# v0_5_0.net
KiCad netlist of a schematic drawn in EAGLE
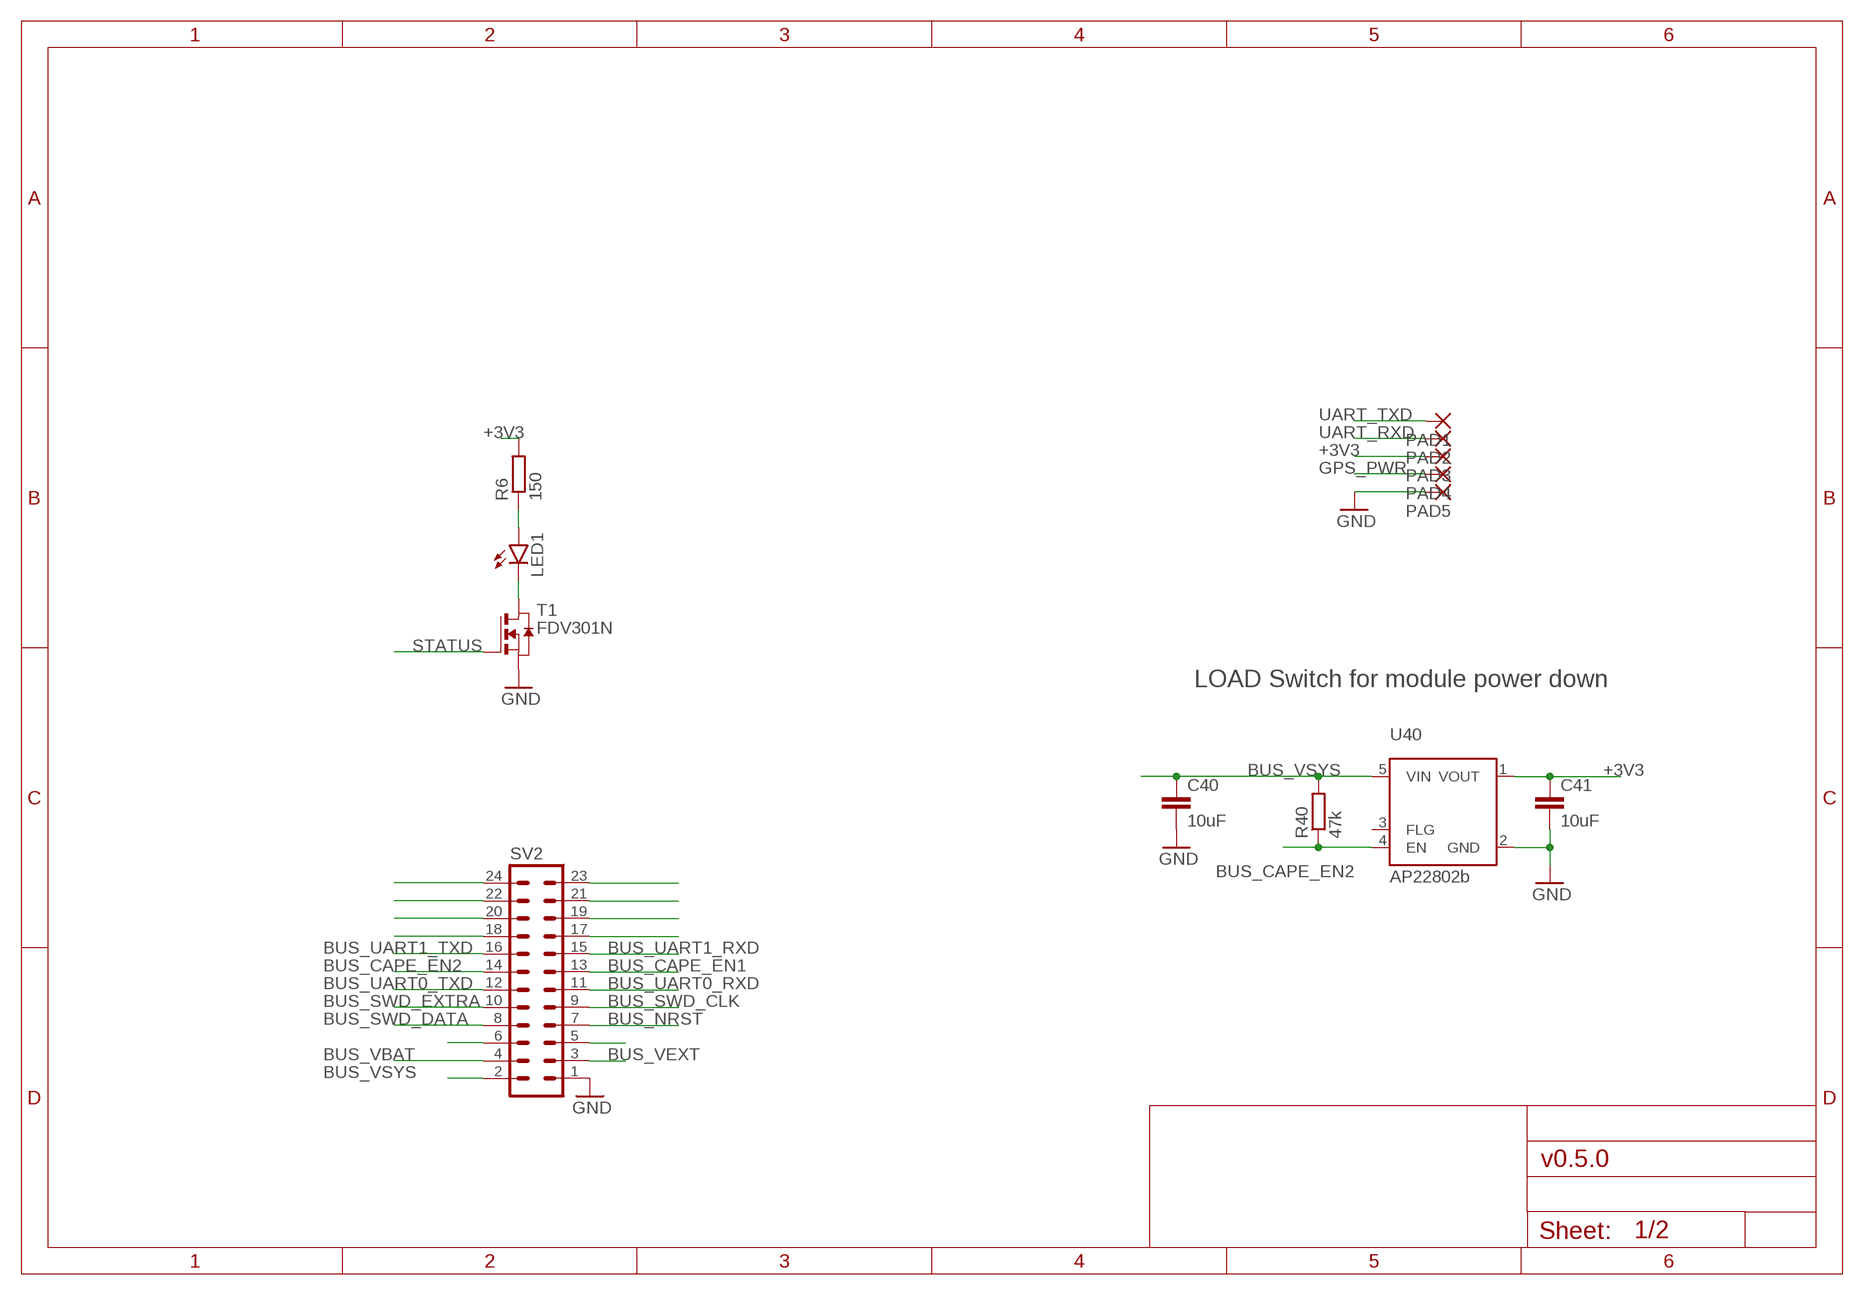
[diagram p0: schematic, sheet 1]
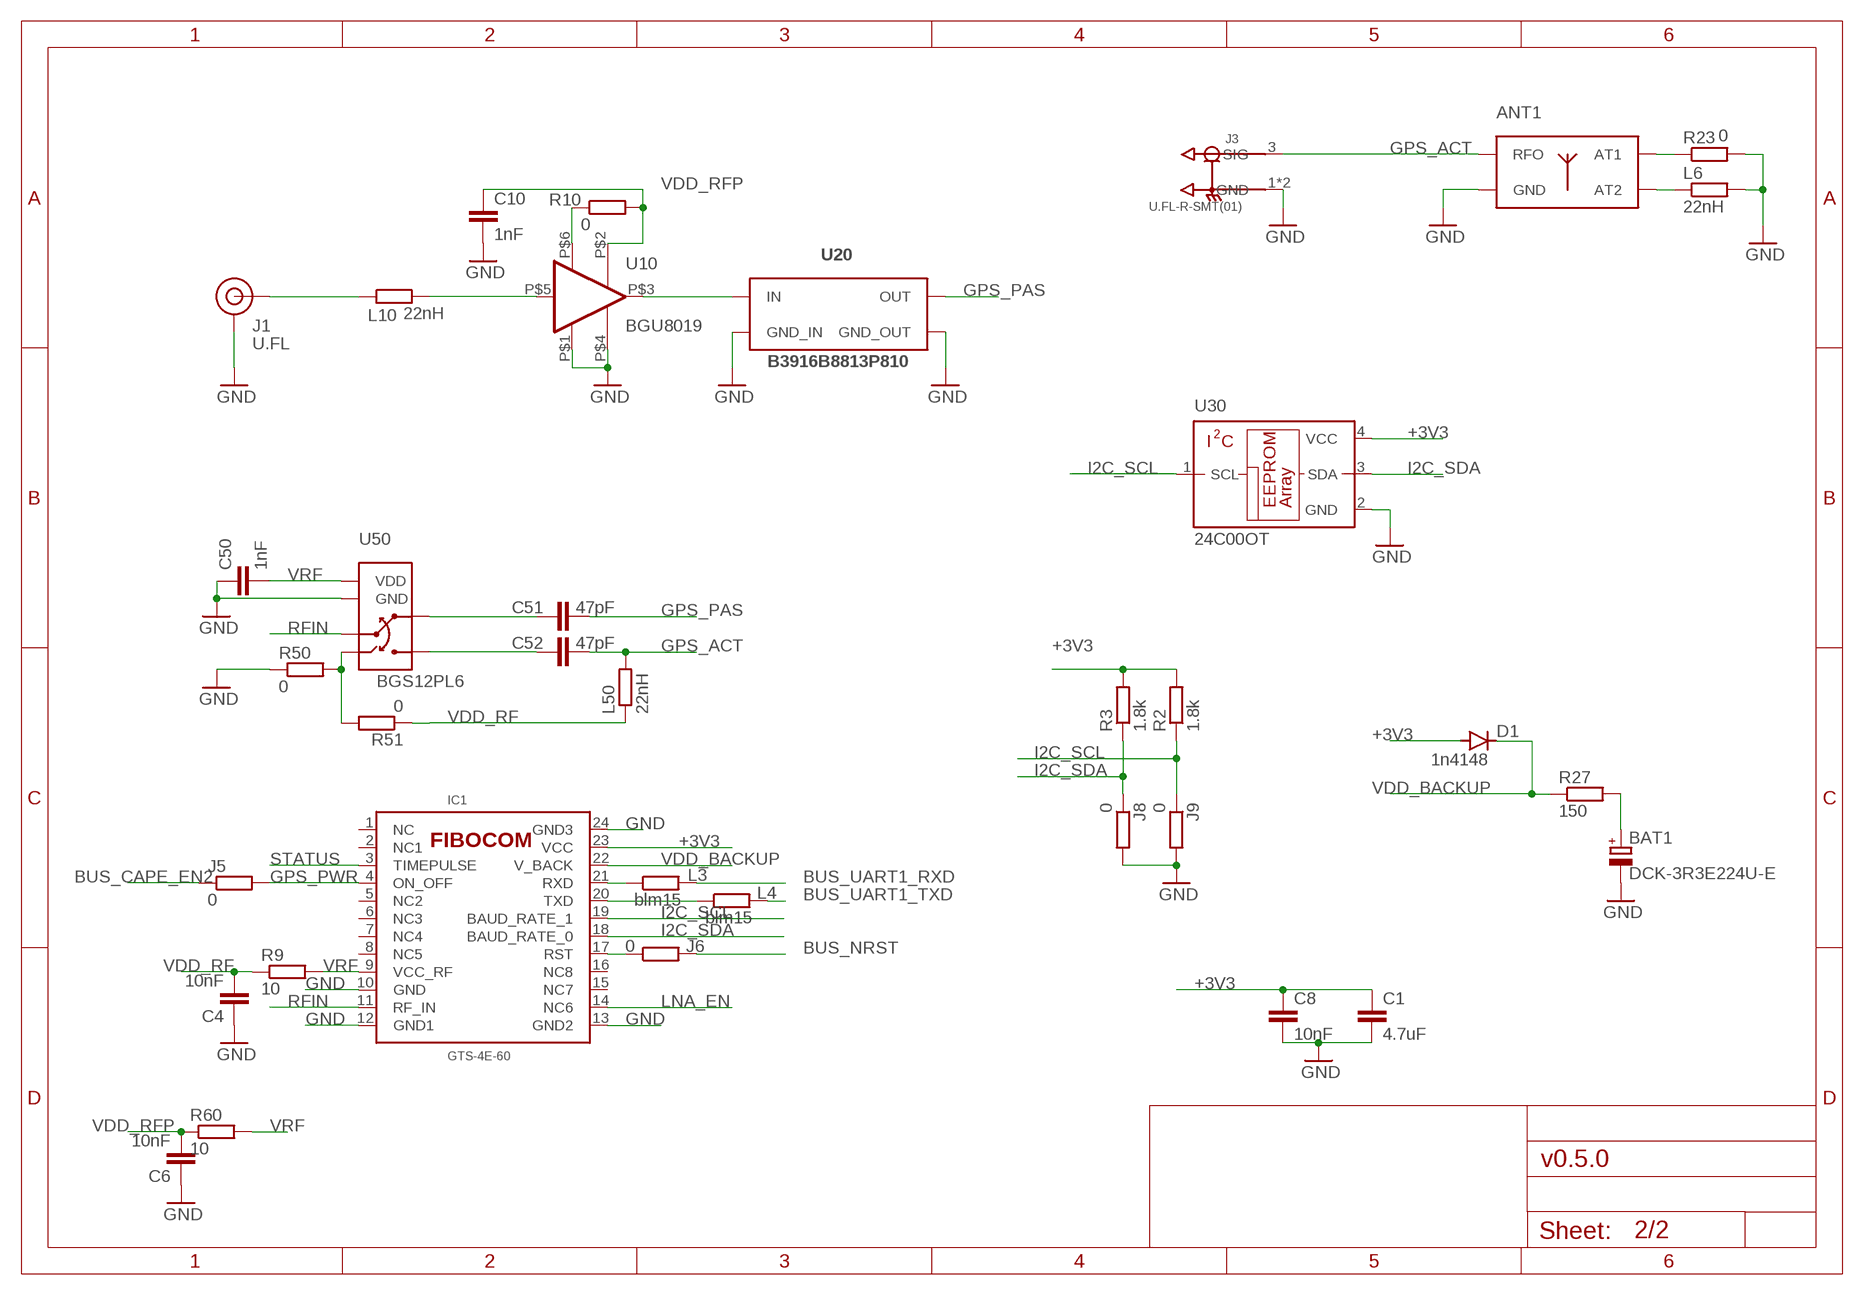
[diagram p1: schematic, sheet 2]

(export (version "E")
  (design (tool "Eeschema 10.0.6"))
  (components
    (comp (ref "C40")
      (value "10uF")
      (footprint "eagle-import:C0603")
      (libsource (lib "eagle-import") (part "C-EUC0603"))
    )
    (comp (ref "C41")
      (value "10uF")
      (footprint "eagle-import:C0603")
      (libsource (lib "eagle-import") (part "C-EUC0603"))
    )
    (comp (ref "LED1")
      (value "LEDCHIP-LED0603")
      (footprint "eagle-import:CHIP-LED0603")
      (libsource (lib "eagle-import") (part "LEDCHIP-LED0603"))
    )
    (comp (ref "PAD1")
      (value "1,6/0,9")
      (footprint "eagle-import:1,6_0,9")
      (libsource (lib "eagle-import") (part "1,6/0,9"))
    )
    (comp (ref "PAD2")
      (value "1,6/0,9")
      (footprint "eagle-import:1,6_0,9")
      (libsource (lib "eagle-import") (part "1,6/0,9"))
    )
    (comp (ref "PAD3")
      (value "1,6/0,9")
      (footprint "eagle-import:1,6_0,9")
      (libsource (lib "eagle-import") (part "1,6/0,9"))
    )
    (comp (ref "PAD4")
      (value "1,6/0,9")
      (footprint "eagle-import:1,6_0,9")
      (libsource (lib "eagle-import") (part "1,6/0,9"))
    )
    (comp (ref "PAD5")
      (value "1,6/0,9")
      (footprint "eagle-import:1,6_0,9")
      (libsource (lib "eagle-import") (part "1,6/0,9"))
    )
    (comp (ref "R6")
      (value "150")
      (footprint "eagle-import:R0402")
      (libsource (lib "eagle-import") (part "R-EU_R0402"))
    )
    (comp (ref "R40")
      (value "47k")
      (footprint "eagle-import:R0402")
      (libsource (lib "eagle-import") (part "R-EU_R0402"))
    )
    (comp (ref "SV2")
      (value "MA12-2")
      (footprint "eagle-import:MA12-2")
      (libsource (lib "eagle-import") (part "MA12-2"))
    )
    (comp (ref "T1")
      (value "FDV301N")
      (footprint "eagle-import:SOT-23")
      (libsource (lib "eagle-import") (part "NMOSSOT23"))
    )
    (comp (ref "U40")
      (value "AP22802b")
      (footprint "eagle-import:SOT25")
      (libsource (lib "eagle-import") (part "AP22802"))
    )
    (comp (ref "ANT1")
      (value "M20047")
      (footprint "eagle-import:PCBCOMPONENT_1")
      (libsource (lib "eagle-import") (part "M20047"))
    )
    (comp (ref "BAT1")
      (value "DCK-3R3E224U-E")
      (footprint "eagle-import:621")
      (libsource (lib "eagle-import") (part "DCK-3R3E224U-E"))
    )
    (comp (ref "C1")
      (value "4.7uF")
      (footprint "eagle-import:C0603")
      (libsource (lib "eagle-import") (part "C-EUC0603"))
    )
    (comp (ref "C4")
      (value "10nF")
      (footprint "eagle-import:C0402")
      (libsource (lib "eagle-import") (part "C-EUC0402"))
    )
    (comp (ref "C6")
      (value "10nF")
      (footprint "eagle-import:C0402")
      (libsource (lib "eagle-import") (part "C-EUC0402"))
    )
    (comp (ref "C8")
      (value "10nF")
      (footprint "eagle-import:C0402")
      (libsource (lib "eagle-import") (part "C-EUC0402"))
    )
    (comp (ref "C10")
      (value "1nF")
      (footprint "eagle-import:C0402")
      (libsource (lib "eagle-import") (part "C-EUC0402"))
    )
    (comp (ref "C50")
      (value "1nF")
      (footprint "eagle-import:C0402")
      (libsource (lib "eagle-import") (part "C-EUC0402"))
    )
    (comp (ref "C51")
      (value "47pF")
      (footprint "eagle-import:C0402")
      (libsource (lib "eagle-import") (part "C-EUC0402"))
    )
    (comp (ref "C52")
      (value "47pF")
      (footprint "eagle-import:C0402")
      (libsource (lib "eagle-import") (part "C-EUC0402"))
    )
    (comp (ref "D1")
      (value "1n4148")
      (footprint "eagle-import:SOD323-R")
      (libsource (lib "eagle-import") (part "DIODE-SOD323-R"))
    )
    (comp (ref "IC1")
      (value "GTS-4E-60")
      (footprint "eagle-import:_GTS_4E_60")
      (libsource (lib "eagle-import") (part "GTS-4E-60"))
    )
    (comp (ref "J1")
      (value "U.FL")
      (footprint "eagle-import:U.FL")
      (libsource (lib "eagle-import") (part "U.FL2PIN"))
    )
    (comp (ref "J3")
      (value "U.FL-R-SMT(01)")
      (footprint "eagle-import:HRS_U.FL-R-SMT(01)")
      (fields (field (name "MF") "Hirose") (field (name "MP") "U.FL-R-SMT_01_"))
      (libsource (lib "eagle-import") (part "U.FL-R-SMT(01)"))
    )
    (comp (ref "J5")
      (value "0")
      (footprint "eagle-import:R0402")
      (libsource (lib "eagle-import") (part "R-EU_R0402"))
    )
    (comp (ref "J6")
      (value "0")
      (footprint "eagle-import:R0402")
      (libsource (lib "eagle-import") (part "R-EU_R0402"))
    )
    (comp (ref "J8")
      (value "0")
      (footprint "eagle-import:R0402")
      (libsource (lib "eagle-import") (part "R-EU_R0402"))
    )
    (comp (ref "J9")
      (value "0")
      (footprint "eagle-import:R0402")
      (libsource (lib "eagle-import") (part "R-EU_R0402"))
    )
    (comp (ref "L3")
      (value "blm15")
      (footprint "eagle-import:R0402")
      (libsource (lib "eagle-import") (part "R-EU_R0402"))
    )
    (comp (ref "L4")
      (value "blm15")
      (footprint "eagle-import:R0402")
      (libsource (lib "eagle-import") (part "R-EU_R0402"))
    )
    (comp (ref "L6")
      (value "22nH")
      (footprint "eagle-import:R0402")
      (libsource (lib "eagle-import") (part "R-EU_R0402"))
    )
    (comp (ref "L10")
      (value "22nH")
      (footprint "eagle-import:R0402")
      (libsource (lib "eagle-import") (part "R-EU_R0402"))
    )
    (comp (ref "L50")
      (value "22nH")
      (footprint "eagle-import:R0402")
      (libsource (lib "eagle-import") (part "R-EU_R0402"))
    )
    (comp (ref "R2")
      (value "1.8k")
      (footprint "eagle-import:R0402")
      (libsource (lib "eagle-import") (part "R-EU_R0402"))
    )
    (comp (ref "R3")
      (value "1.8k")
      (footprint "eagle-import:R0402")
      (libsource (lib "eagle-import") (part "R-EU_R0402"))
    )
    (comp (ref "R9")
      (value "10")
      (footprint "eagle-import:R0402")
      (libsource (lib "eagle-import") (part "R-EU_R0402"))
    )
    (comp (ref "R10")
      (value "0")
      (footprint "eagle-import:R0402")
      (libsource (lib "eagle-import") (part "R-EU_R0402"))
    )
    (comp (ref "R23")
      (value "0")
      (footprint "eagle-import:R0402")
      (libsource (lib "eagle-import") (part "R-EU_R0402"))
    )
    (comp (ref "R27")
      (value "150")
      (footprint "eagle-import:R0402")
      (libsource (lib "eagle-import") (part "R-EU_R0402"))
    )
    (comp (ref "R50")
      (value "0")
      (footprint "eagle-import:R0402")
      (libsource (lib "eagle-import") (part "R-EU_R0402"))
    )
    (comp (ref "R51")
      (value "0")
      (footprint "eagle-import:R0402")
      (libsource (lib "eagle-import") (part "R-EU_R0402"))
    )
    (comp (ref "R60")
      (value "10")
      (footprint "eagle-import:R0402")
      (libsource (lib "eagle-import") (part "R-EU_R0402"))
    )
    (comp (ref "U10")
      (value "BGU8019")
      (footprint "eagle-import:XSON6")
      (libsource (lib "eagle-import") (part "BGU8019"))
    )
    (comp (ref "U20")
      (value "B3916B8813P810")
      (footprint "eagle-import:XSON5")
      (libsource (lib "eagle-import") (part "B3916B8813P810"))
    )
    (comp (ref "U30")
      (value "24C00OT")
      (footprint "eagle-import:SOT23-5L")
      (fields (field (name "MF") "MICROCHIP") (field (name "MPN") "24C00T-I/OT"))
      (libsource (lib "eagle-import") (part "2400OTC"))
    )
    (comp (ref "U50")
      (value "BGS12PL6")
      (footprint "eagle-import:TSLP-6-4")
      (libsource (lib "eagle-import") (part "BGS12PL6"))
    )
  )
  (nets
    (net (code "1") (name "+3V3") (class "Default")
      (node (ref "C1") (pin "1") (pinfunction "1_1") (pintype "passive"))
      (node (ref "C41") (pin "1") (pinfunction "1_1") (pintype "passive"))
      (node (ref "C8") (pin "1") (pinfunction "1_1") (pintype "passive"))
      (node (ref "D1") (pin "A") (pinfunction "A_A") (pintype "passive"))
      (node (ref "IC1") (pin "23") (pinfunction "VCC_23") (pintype "bidirectional"))
      (node (ref "PAD3") (pin "1") (pinfunction "P_1") (pintype "passive"))
      (node (ref "R2") (pin "2") (pinfunction "2_2") (pintype "passive"))
      (node (ref "R3") (pin "2") (pinfunction "2_2") (pintype "passive"))
      (node (ref "R6") (pin "2") (pinfunction "2_2") (pintype "passive"))
      (node (ref "U30") (pin "4") (pinfunction "VCC_4") (pintype "power_in"))
      (node (ref "U40") (pin "1") (pinfunction "VOUT_1") (pintype "bidirectional"))
    )
    (net (code "2") (name "BUS_CAPE_EN1") (class "Default")
      (node (ref "SV2") (pin "13") (pinfunction "13_13") (pintype "passive"))
    )
    (net (code "3") (name "BUS_CAPE_EN2") (class "Default")
      (node (ref "J5") (pin "1") (pinfunction "1_1") (pintype "passive"))
      (node (ref "R40") (pin "1") (pinfunction "1_1") (pintype "passive"))
      (node (ref "SV2") (pin "14") (pinfunction "14_14") (pintype "passive"))
      (node (ref "U40") (pin "4") (pinfunction "EN_4") (pintype "bidirectional"))
    )
    (net (code "4") (name "BUS_NRST") (class "Default")
      (node (ref "J6") (pin "2") (pinfunction "2_2") (pintype "passive"))
      (node (ref "SV2") (pin "7") (pinfunction "7_7") (pintype "passive"))
    )
    (net (code "5") (name "BUS_SWD_CLK") (class "Default")
      (node (ref "SV2") (pin "9") (pinfunction "9_9") (pintype "passive"))
    )
    (net (code "6") (name "BUS_SWD_DATA") (class "Default")
      (node (ref "SV2") (pin "8") (pinfunction "8_8") (pintype "passive"))
    )
    (net (code "7") (name "BUS_SWD_EXTRA") (class "Default")
      (node (ref "SV2") (pin "10") (pinfunction "10_10") (pintype "passive"))
    )
    (net (code "8") (name "BUS_UART0_RXD") (class "Default")
      (node (ref "SV2") (pin "11") (pinfunction "11_11") (pintype "passive"))
    )
    (net (code "9") (name "BUS_UART0_TXD") (class "Default")
      (node (ref "SV2") (pin "12") (pinfunction "12_12") (pintype "passive"))
    )
    (net (code "10") (name "BUS_UART1_RXD") (class "Default")
      (node (ref "L3") (pin "2") (pinfunction "2_2") (pintype "passive"))
      (node (ref "SV2") (pin "15") (pinfunction "15_15") (pintype "passive"))
    )
    (net (code "11") (name "BUS_UART1_TXD") (class "Default")
      (node (ref "L4") (pin "2") (pinfunction "2_2") (pintype "passive"))
      (node (ref "SV2") (pin "16") (pinfunction "16_16") (pintype "passive"))
    )
    (net (code "12") (name "BUS_VBAT") (class "Default")
      (node (ref "SV2") (pin "4") (pinfunction "4_4") (pintype "passive"))
    )
    (net (code "13") (name "BUS_VEXT") (class "Default")
      (node (ref "SV2") (pin "3") (pinfunction "3_3") (pintype "passive"))
    )
    (net (code "14") (name "BUS_VSYS") (class "Default")
      (node (ref "C40") (pin "1") (pinfunction "1_1") (pintype "passive"))
      (node (ref "R40") (pin "2") (pinfunction "2_2") (pintype "passive"))
      (node (ref "SV2") (pin "2") (pinfunction "2_2") (pintype "passive"))
      (node (ref "U40") (pin "5") (pinfunction "VIN_5") (pintype "bidirectional"))
    )
    (net (code "15") (name "GND") (class "Default")
      (node (ref "ANT1") (pin "2") (pinfunction "GND_2") (pintype "power_in"))
      (node (ref "ANT1") (pin "3") (pinfunction "GND_3") (pintype "power_in"))
      (node (ref "ANT1") (pin "4") (pinfunction "GND_4") (pintype "power_in"))
      (node (ref "BAT1") (pin "-") (pinfunction "-_-") (pintype "passive"))
      (node (ref "C1") (pin "2") (pinfunction "2_2") (pintype "passive"))
      (node (ref "C10") (pin "2") (pinfunction "2_2") (pintype "passive"))
      (node (ref "C4") (pin "1") (pinfunction "1_1") (pintype "passive"))
      (node (ref "C40") (pin "2") (pinfunction "2_2") (pintype "passive"))
      (node (ref "C41") (pin "2") (pinfunction "2_2") (pintype "passive"))
      (node (ref "C50") (pin "1") (pinfunction "1_1") (pintype "passive"))
      (node (ref "C6") (pin "1") (pinfunction "1_1") (pintype "passive"))
      (node (ref "C8") (pin "2") (pinfunction "2_2") (pintype "passive"))
      (node (ref "IC1") (pin "10") (pinfunction "GND_10") (pintype "bidirectional"))
      (node (ref "IC1") (pin "12") (pinfunction "GND1_12") (pintype "bidirectional"))
      (node (ref "IC1") (pin "13") (pinfunction "GND2_13") (pintype "bidirectional"))
      (node (ref "IC1") (pin "24") (pinfunction "GND3_24") (pintype "bidirectional"))
      (node (ref "J1") (pin "1") (pinfunction "GND_1") (pintype "bidirectional"))
      (node (ref "J1") (pin "2") (pinfunction "GND_2") (pintype "bidirectional"))
      (node (ref "J3") (pin "1") (pinfunction "GND_1") (pintype "passive"))
      (node (ref "J3") (pin "2") (pinfunction "GND_2") (pintype "passive"))
      (node (ref "J8") (pin "2") (pinfunction "2_2") (pintype "passive"))
      (node (ref "J9") (pin "2") (pinfunction "2_2") (pintype "passive"))
      (node (ref "L6") (pin "2") (pinfunction "2_2") (pintype "passive"))
      (node (ref "PAD5") (pin "1") (pinfunction "P_1") (pintype "passive"))
      (node (ref "R23") (pin "2") (pinfunction "2_2") (pintype "passive"))
      (node (ref "R50") (pin "1") (pinfunction "1_1") (pintype "passive"))
      (node (ref "SV2") (pin "1") (pinfunction "1_1") (pintype "passive"))
      (node (ref "T1") (pin "2") (pinfunction "S_2") (pintype "passive"))
      (node (ref "U10") (pin "P$1") (pinfunction "GND_P$1") (pintype "power_in"))
      (node (ref "U10") (pin "P$4") (pinfunction "GND_RF_P$4") (pintype "passive"))
      (node (ref "U20") (pin "2") (pinfunction "GND_IN_2") (pintype "bidirectional"))
      (node (ref "U20") (pin "3") (pinfunction "GND_OUT_3") (pintype "bidirectional"))
      (node (ref "U20") (pin "5") (pinfunction "GND_IN_5") (pintype "bidirectional"))
      (node (ref "U30") (pin "2") (pinfunction "GND_2") (pintype "power_in"))
      (node (ref "U40") (pin "2") (pinfunction "GND_2") (pintype "bidirectional"))
      (node (ref "U50") (pin "P$2") (pinfunction "GND_P$2") (pintype "power_in"))
    )
    (net (code "16") (name "GPS_ACT") (class "Default")
      (node (ref "ANT1") (pin "5") (pinfunction "RFO_5") (pintype "input"))
      (node (ref "C52") (pin "2") (pinfunction "2_2") (pintype "passive"))
      (node (ref "J3") (pin "3") (pinfunction "SIG_3") (pintype "passive"))
      (node (ref "L50") (pin "2") (pinfunction "2_2") (pintype "passive"))
    )
    (net (code "17") (name "GPS_PAS") (class "Default")
      (node (ref "C51") (pin "2") (pinfunction "2_2") (pintype "passive"))
      (node (ref "U20") (pin "4") (pinfunction "OUT_4") (pintype "bidirectional"))
    )
    (net (code "18") (name "GPS_PWR") (class "Default")
      (node (ref "IC1") (pin "4") (pinfunction "ON_OFF_4") (pintype "bidirectional"))
      (node (ref "J5") (pin "2") (pinfunction "2_2") (pintype "passive"))
      (node (ref "PAD4") (pin "1") (pinfunction "P_1") (pintype "passive"))
    )
    (net (code "19") (name "I2C_SCL") (class "Default")
      (node (ref "IC1") (pin "19") (pinfunction "BAUD_RATE_1_19") (pintype "bidirectional"))
      (node (ref "J9") (pin "1") (pinfunction "1_1") (pintype "passive"))
      (node (ref "R2") (pin "1") (pinfunction "1_1") (pintype "passive"))
      (node (ref "U30") (pin "1") (pinfunction "SCL_1") (pintype "input"))
    )
    (net (code "20") (name "I2C_SDA") (class "Default")
      (node (ref "IC1") (pin "18") (pinfunction "BAUD_RATE_0_18") (pintype "bidirectional"))
      (node (ref "J8") (pin "1") (pinfunction "1_1") (pintype "passive"))
      (node (ref "R3") (pin "1") (pinfunction "1_1") (pintype "passive"))
      (node (ref "U30") (pin "3") (pinfunction "SDA_3") (pintype "bidirectional"))
    )
    (net (code "21") (name "LNA_EN") (class "Default")
      (node (ref "IC1") (pin "14") (pinfunction "NC6_14") (pintype "bidirectional"))
    )
    (net (code "22") (name "Net-(ANT1-AT1)") (class "Default")
      (node (ref "ANT1") (pin "1") (pinfunction "AT1_1") (pintype "bidirectional"))
      (node (ref "R23") (pin "1") (pinfunction "1_1") (pintype "passive"))
    )
    (net (code "23") (name "Net-(ANT1-AT2)") (class "Default")
      (node (ref "ANT1") (pin "6") (pinfunction "AT2_6") (pintype "bidirectional"))
      (node (ref "L6") (pin "1") (pinfunction "1_1") (pintype "passive"))
    )
    (net (code "24") (name "Net-(BAT1-Pad+)") (class "Default")
      (node (ref "BAT1") (pin "+") (pinfunction "+_+") (pintype "passive"))
      (node (ref "R27") (pin "2") (pinfunction "2_2") (pintype "passive"))
    )
    (net (code "25") (name "Net-(IC1-RST)") (class "Default")
      (node (ref "IC1") (pin "17") (pinfunction "RST_17") (pintype "bidirectional"))
      (node (ref "J6") (pin "1") (pinfunction "1_1") (pintype "passive"))
    )
    (net (code "26") (name "Net-(J1-SIGNAL)") (class "Default")
      (node (ref "J1") (pin "FEED") (pinfunction "SIGNAL_FEED") (pintype "bidirectional"))
      (node (ref "L10") (pin "1") (pinfunction "1_1") (pintype "passive"))
    )
    (net (code "27") (name "Net-(LED1-PadA)") (class "Default")
      (node (ref "LED1") (pin "A") (pinfunction "A_A") (pintype "passive"))
      (node (ref "R6") (pin "1") (pinfunction "1_1") (pintype "passive"))
    )
    (net (code "28") (name "Net-(T1-D)") (class "Default")
      (node (ref "LED1") (pin "C") (pinfunction "C_C") (pintype "passive"))
      (node (ref "T1") (pin "1") (pinfunction "D_1") (pintype "passive"))
    )
    (net (code "29") (name "Net-(U10-ENABLE)") (class "Default")
      (node (ref "R10") (pin "1") (pinfunction "1_1") (pintype "passive"))
      (node (ref "U10") (pin "P$6") (pinfunction "ENABLE_P$6") (pintype "power_in"))
    )
    (net (code "30") (name "Net-(U10-RF_IN)") (class "Default")
      (node (ref "L10") (pin "2") (pinfunction "2_2") (pintype "passive"))
      (node (ref "U10") (pin "P$5") (pinfunction "RF_IN_P$5") (pintype "input"))
    )
    (net (code "31") (name "Net-(U10-RF_OUT)") (class "Default")
      (node (ref "U10") (pin "P$3") (pinfunction "RF_OUT_P$3") (pintype "output"))
      (node (ref "U20") (pin "1") (pinfunction "IN_1") (pintype "bidirectional"))
    )
    (net (code "32") (name "Net-(U50-P$4)") (class "Default")
      (node (ref "R50") (pin "2") (pinfunction "2_2") (pintype "passive"))
      (node (ref "R51") (pin "2") (pinfunction "2_2") (pintype "passive"))
      (node (ref "U50") (pin "P$6") (pinfunction "P$4_P$6") (pintype "bidirectional"))
    )
    (net (code "33") (name "Net-(U50-RF1)") (class "Default")
      (node (ref "C51") (pin "1") (pinfunction "1_1") (pintype "passive"))
      (node (ref "U50") (pin "P$3") (pinfunction "RF1_P$3") (pintype "bidirectional"))
    )
    (net (code "34") (name "Net-(U50-RF2)") (class "Default")
      (node (ref "C52") (pin "1") (pinfunction "1_1") (pintype "passive"))
      (node (ref "U50") (pin "P$1") (pinfunction "RF2_P$1") (pintype "bidirectional"))
    )
    (net (code "35") (name "RFIN") (class "Default")
      (node (ref "IC1") (pin "11") (pinfunction "RF_IN_11") (pintype "bidirectional"))
      (node (ref "U50") (pin "P$5") (pinfunction "RFIN_P$5") (pintype "bidirectional"))
    )
    (net (code "36") (name "STATUS") (class "Default")
      (node (ref "IC1") (pin "3") (pinfunction "TIMEPULSE_3") (pintype "bidirectional"))
      (node (ref "T1") (pin "3") (pinfunction "G_3") (pintype "passive"))
    )
    (net (code "37") (name "UART_RXD") (class "Default")
      (node (ref "IC1") (pin "20") (pinfunction "TXD_20") (pintype "bidirectional"))
      (node (ref "L4") (pin "1") (pinfunction "1_1") (pintype "passive"))
      (node (ref "PAD2") (pin "1") (pinfunction "P_1") (pintype "passive"))
    )
    (net (code "38") (name "UART_TXD") (class "Default")
      (node (ref "IC1") (pin "21") (pinfunction "RXD_21") (pintype "bidirectional"))
      (node (ref "L3") (pin "1") (pinfunction "1_1") (pintype "passive"))
      (node (ref "PAD1") (pin "1") (pinfunction "P_1") (pintype "passive"))
    )
    (net (code "39") (name "VDD_BACKUP") (class "Default")
      (node (ref "D1") (pin "C") (pinfunction "C_C") (pintype "passive"))
      (node (ref "IC1") (pin "22") (pinfunction "V_BACK_22") (pintype "bidirectional"))
      (node (ref "R27") (pin "1") (pinfunction "1_1") (pintype "passive"))
    )
    (net (code "40") (name "VDD_RF") (class "Default")
      (node (ref "C4") (pin "2") (pinfunction "2_2") (pintype "passive"))
      (node (ref "L50") (pin "1") (pinfunction "1_1") (pintype "passive"))
      (node (ref "R51") (pin "1") (pinfunction "1_1") (pintype "passive"))
      (node (ref "R9") (pin "1") (pinfunction "1_1") (pintype "passive"))
    )
    (net (code "41") (name "VDD_RFP") (class "Default")
      (node (ref "C10") (pin "1") (pinfunction "1_1") (pintype "passive"))
      (node (ref "C6") (pin "2") (pinfunction "2_2") (pintype "passive"))
      (node (ref "R10") (pin "2") (pinfunction "2_2") (pintype "passive"))
      (node (ref "R60") (pin "1") (pinfunction "1_1") (pintype "passive"))
      (node (ref "U10") (pin "P$2") (pinfunction "VCC_P$2") (pintype "passive"))
    )
    (net (code "42") (name "VRF") (class "Default")
      (node (ref "C50") (pin "2") (pinfunction "2_2") (pintype "passive"))
      (node (ref "IC1") (pin "9") (pinfunction "VCC_RF_9") (pintype "bidirectional"))
      (node (ref "R60") (pin "2") (pinfunction "2_2") (pintype "passive"))
      (node (ref "R9") (pin "2") (pinfunction "2_2") (pintype "passive"))
      (node (ref "U50") (pin "P$4") (pinfunction "VDD_P$4") (pintype "power_in"))
    )
    (net (code "43") (name "unconnected-(IC1-NC-Pad1)") (class "Default")
      (node (ref "IC1") (pin "1") (pinfunction "NC_1") (pintype "bidirectional"))
    )
    (net (code "44") (name "unconnected-(IC1-NC1-Pad2)") (class "Default")
      (node (ref "IC1") (pin "2") (pinfunction "NC1_2") (pintype "bidirectional"))
    )
    (net (code "45") (name "unconnected-(IC1-NC2-Pad5)") (class "Default")
      (node (ref "IC1") (pin "5") (pinfunction "NC2_5") (pintype "bidirectional"))
    )
    (net (code "46") (name "unconnected-(IC1-NC3-Pad6)") (class "Default")
      (node (ref "IC1") (pin "6") (pinfunction "NC3_6") (pintype "bidirectional"))
    )
    (net (code "47") (name "unconnected-(IC1-NC4-Pad7)") (class "Default")
      (node (ref "IC1") (pin "7") (pinfunction "NC4_7") (pintype "bidirectional"))
    )
    (net (code "48") (name "unconnected-(IC1-NC5-Pad8)") (class "Default")
      (node (ref "IC1") (pin "8") (pinfunction "NC5_8") (pintype "bidirectional"))
    )
    (net (code "49") (name "unconnected-(IC1-NC7-Pad15)") (class "Default")
      (node (ref "IC1") (pin "15") (pinfunction "NC7_15") (pintype "bidirectional"))
    )
    (net (code "50") (name "unconnected-(IC1-NC8-Pad16)") (class "Default")
      (node (ref "IC1") (pin "16") (pinfunction "NC8_16") (pintype "bidirectional"))
    )
    (net (code "51") (name "unconnected-(SV2-Pad5)") (class "Default")
      (node (ref "SV2") (pin "5") (pinfunction "5_5") (pintype "passive"))
    )
    (net (code "52") (name "unconnected-(SV2-Pad6)") (class "Default")
      (node (ref "SV2") (pin "6") (pinfunction "6_6") (pintype "passive"))
    )
    (net (code "53") (name "unconnected-(SV2-Pad17)") (class "Default")
      (node (ref "SV2") (pin "17") (pinfunction "17_17") (pintype "passive"))
    )
    (net (code "54") (name "unconnected-(SV2-Pad18)") (class "Default")
      (node (ref "SV2") (pin "18") (pinfunction "18_18") (pintype "passive"))
    )
    (net (code "55") (name "unconnected-(SV2-Pad19)") (class "Default")
      (node (ref "SV2") (pin "19") (pinfunction "19_19") (pintype "passive"))
    )
    (net (code "56") (name "unconnected-(SV2-Pad20)") (class "Default")
      (node (ref "SV2") (pin "20") (pinfunction "20_20") (pintype "passive"))
    )
    (net (code "57") (name "unconnected-(SV2-Pad21)") (class "Default")
      (node (ref "SV2") (pin "21") (pinfunction "21_21") (pintype "passive"))
    )
    (net (code "58") (name "unconnected-(SV2-Pad22)") (class "Default")
      (node (ref "SV2") (pin "22") (pinfunction "22_22") (pintype "passive"))
    )
    (net (code "59") (name "unconnected-(SV2-Pad23)") (class "Default")
      (node (ref "SV2") (pin "23") (pinfunction "23_23") (pintype "passive"))
    )
    (net (code "60") (name "unconnected-(SV2-Pad24)") (class "Default")
      (node (ref "SV2") (pin "24") (pinfunction "24_24") (pintype "passive"))
    )
    (net (code "61") (name "unconnected-(U40-FLG-Pad3)") (class "Default")
      (node (ref "U40") (pin "3") (pinfunction "FLG_3") (pintype "bidirectional"))
    )
  )
)
